# tick-shield-mk-1_2.net
KiCad netlist of a schematic drawn in EAGLE
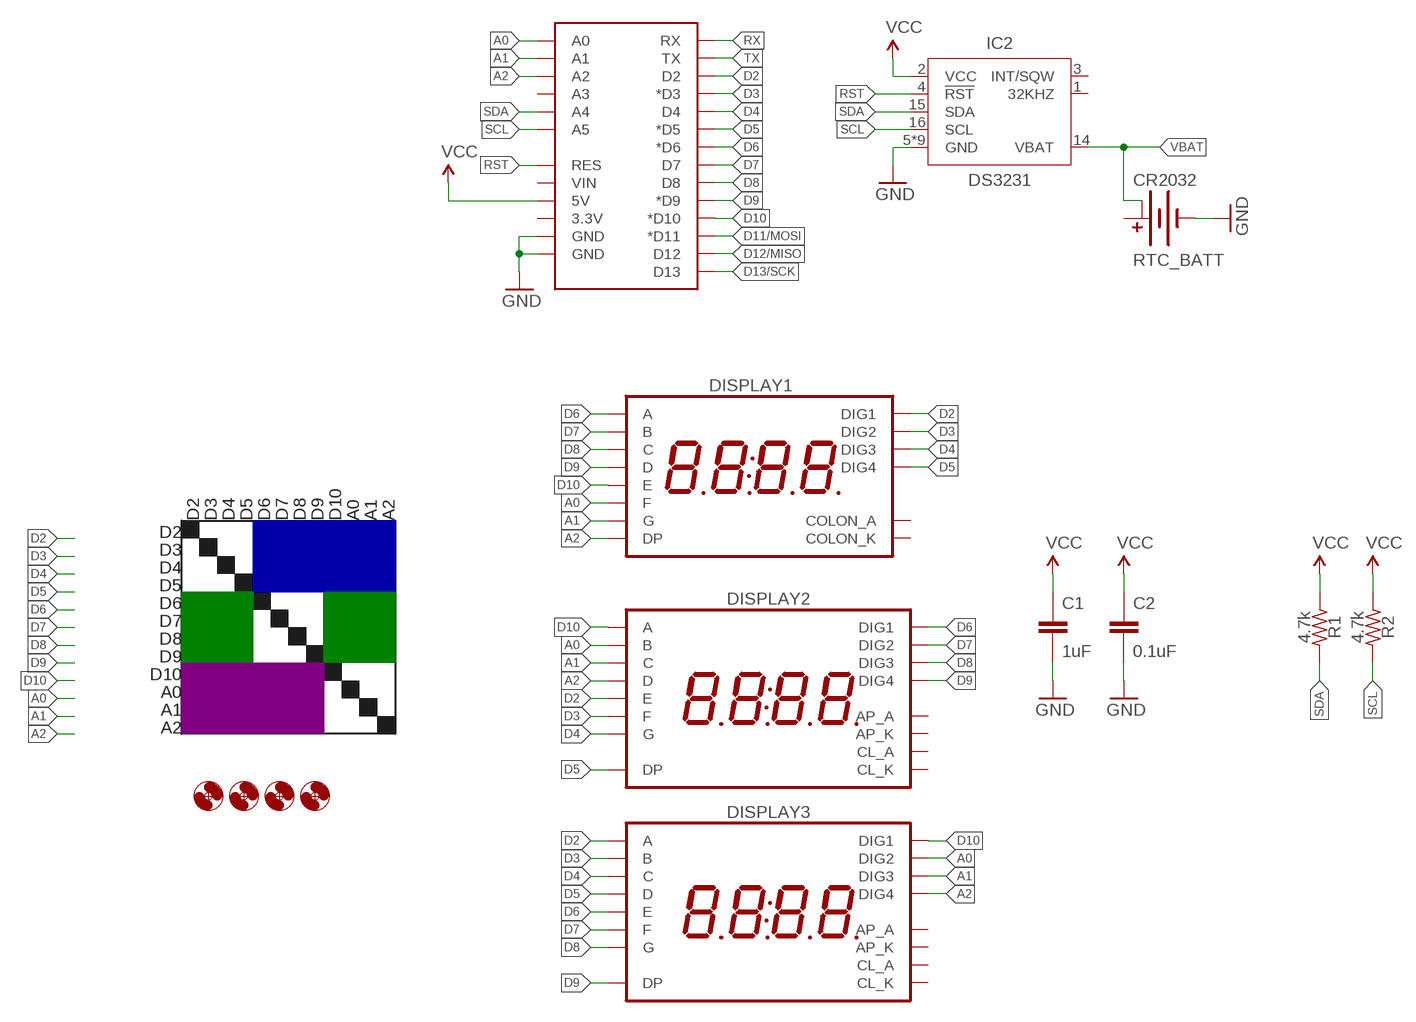
[diagram p0: schematic, sheet 1]

(export (version "E")
  (design (tool "Eeschema 10.0.6"))
  (components
    (comp (ref "C1")
      (value "1uF")
      (footprint "eagle-import:C025-024X044")
      (libsource (lib "eagle-import") (part "CAPACITOR-CERAMIC025-024X044"))
    )
    (comp (ref "C2")
      (value "0.1uF")
      (footprint "eagle-import:C0805")
      (libsource (lib "eagle-import") (part "CAPACITOR-CERAMICC0805"))
    )
    (comp (ref "DISPLAY1")
      (value "7SEG_4DIGIT_COLON14.2MM-CC-NS")
      (footprint "eagle-import:7SEG_4DIG_NS")
      (libsource (lib "eagle-import") (part "7SEG_4DIGIT_COLON14.2MM-CC-NS"))
    )
    (comp (ref "DISPLAY2")
      (value "7SEG_4DIGIT_COLON_APOS")
      (footprint "eagle-import:7SEG_4DIG_10MM")
      (libsource (lib "eagle-import") (part "7SEG_4DIGIT_COLON_APOS"))
    )
    (comp (ref "DISPLAY3")
      (value "7SEG_4DIGIT_COLON_APOS")
      (footprint "eagle-import:7SEG_4DIG_10MM")
      (libsource (lib "eagle-import") (part "7SEG_4DIGIT_COLON_APOS"))
    )
    (comp (ref "H1")
      (value "HOLE#2")
      (footprint "eagle-import:HOLE-#2")
      (libsource (lib "eagle-import") (part "HOLE#2"))
    )
    (comp (ref "H2")
      (value "HOLE#2")
      (footprint "eagle-import:HOLE-#2")
      (libsource (lib "eagle-import") (part "HOLE#2"))
    )
    (comp (ref "H3")
      (value "HOLE#2")
      (footprint "eagle-import:HOLE-#2")
      (libsource (lib "eagle-import") (part "HOLE#2"))
    )
    (comp (ref "H4")
      (value "HOLE#2")
      (footprint "eagle-import:HOLE-#2")
      (libsource (lib "eagle-import") (part "HOLE#2"))
    )
    (comp (ref "IC2")
      (value "DS3231")
      (footprint "eagle-import:SO16W")
      (libsource (lib "eagle-import") (part "DS3231"))
    )
    (comp (ref "R1")
      (value "4.7k")
      (footprint "eagle-import:RESISTOR-AXIAL-PTH-6.35MM")
      (libsource (lib "eagle-import") (part "RESISTORPTH-AXIAL-6.35MM"))
    )
    (comp (ref "R2")
      (value "4.7k")
      (footprint "eagle-import:RESISTOR-AXIAL-PTH-6.35MM")
      (libsource (lib "eagle-import") (part "RESISTORPTH-AXIAL-6.35MM"))
    )
    (comp (ref "RTC_BATT")
      (value "CR2032")
      (footprint "eagle-import:BATTCON_20MM_MINE")
      (libsource (lib "eagle-import") (part "BATTERY-COINCR2032_SMD"))
    )
    (comp (ref "U$1")
      (value "ARDUINO_SHIELD_SMALLER")
      (footprint "eagle-import:ARDUINO_SHIELD_NOOUTLINE_INSIDE_SMALLER")
      (libsource (lib "eagle-import") (part "ARDUINO_SHIELD_SMALLER"))
    )
  )
  (nets
    (net (code "1") (name "A0") (class "Default")
      (node (ref "DISPLAY1") (pin "P$12") (pinfunction "F_P$12") (pintype "passive"))
      (node (ref "DISPLAY2") (pin "16") (pinfunction "B_16") (pintype "passive"))
      (node (ref "DISPLAY3") (pin "2") (pinfunction "DIG2_2") (pintype "passive"))
      (node (ref "U$1") (pin "A0") (pinfunction "A0_A0") (pintype "bidirectional"))
    )
    (net (code "2") (name "A1") (class "Default")
      (node (ref "DISPLAY1") (pin "P$5") (pinfunction "G_P$5") (pintype "passive"))
      (node (ref "DISPLAY2") (pin "13") (pinfunction "C_13") (pintype "passive"))
      (node (ref "DISPLAY3") (pin "6") (pinfunction "DIG3_6") (pintype "passive"))
      (node (ref "U$1") (pin "A1") (pinfunction "A1_A1") (pintype "bidirectional"))
    )
    (net (code "3") (name "A2") (class "Default")
      (node (ref "DISPLAY1") (pin "P$3") (pinfunction "DP_P$3") (pintype "passive"))
      (node (ref "DISPLAY2") (pin "3") (pinfunction "D_3") (pintype "passive"))
      (node (ref "DISPLAY3") (pin "8") (pinfunction "DIG4_8") (pintype "passive"))
      (node (ref "U$1") (pin "A2") (pinfunction "A2_A2") (pintype "bidirectional"))
    )
    (net (code "4") (name "D2") (class "Default")
      (node (ref "DISPLAY1") (pin "P$14") (pinfunction "DIG1_P$14") (pintype "passive"))
      (node (ref "DISPLAY2") (pin "5") (pinfunction "E_5") (pintype "passive"))
      (node (ref "DISPLAY3") (pin "14") (pinfunction "A_14") (pintype "passive"))
      (node (ref "U$1") (pin "D2") (pinfunction "D2_D2") (pintype "bidirectional"))
    )
    (net (code "5") (name "D3") (class "Default")
      (node (ref "DISPLAY1") (pin "P$11") (pinfunction "DIG2_P$11") (pintype "passive"))
      (node (ref "DISPLAY2") (pin "11") (pinfunction "F_11") (pintype "passive"))
      (node (ref "DISPLAY3") (pin "16") (pinfunction "B_16") (pintype "passive"))
      (node (ref "U$1") (pin "D3") (pinfunction "*D3_D3") (pintype "bidirectional"))
    )
    (net (code "6") (name "D4") (class "Default")
      (node (ref "DISPLAY1") (pin "P$10") (pinfunction "DIG3_P$10") (pintype "passive"))
      (node (ref "DISPLAY2") (pin "15") (pinfunction "G_15") (pintype "passive"))
      (node (ref "DISPLAY3") (pin "13") (pinfunction "C_13") (pintype "passive"))
      (node (ref "U$1") (pin "D4") (pinfunction "D4_D4") (pintype "bidirectional"))
    )
    (net (code "7") (name "D5") (class "Default")
      (node (ref "DISPLAY1") (pin "P$6") (pinfunction "DIG4_P$6") (pintype "passive"))
      (node (ref "DISPLAY2") (pin "7") (pinfunction "DP_7") (pintype "passive"))
      (node (ref "DISPLAY3") (pin "3") (pinfunction "D_3") (pintype "passive"))
      (node (ref "U$1") (pin "D5") (pinfunction "*D5_D5") (pintype "bidirectional"))
    )
    (net (code "8") (name "D6") (class "Default")
      (node (ref "DISPLAY1") (pin "P$13") (pinfunction "A_P$13") (pintype "passive"))
      (node (ref "DISPLAY2") (pin "1") (pinfunction "DIG1_1") (pintype "passive"))
      (node (ref "DISPLAY3") (pin "5") (pinfunction "E_5") (pintype "passive"))
      (node (ref "U$1") (pin "D6") (pinfunction "*D6_D6") (pintype "bidirectional"))
    )
    (net (code "9") (name "D7") (class "Default")
      (node (ref "DISPLAY1") (pin "P$9") (pinfunction "B_P$9") (pintype "passive"))
      (node (ref "DISPLAY2") (pin "2") (pinfunction "DIG2_2") (pintype "passive"))
      (node (ref "DISPLAY3") (pin "11") (pinfunction "F_11") (pintype "passive"))
      (node (ref "U$1") (pin "D7") (pinfunction "D7_D7") (pintype "bidirectional"))
    )
    (net (code "10") (name "D8") (class "Default")
      (node (ref "DISPLAY1") (pin "P$4") (pinfunction "C_P$4") (pintype "passive"))
      (node (ref "DISPLAY2") (pin "6") (pinfunction "DIG3_6") (pintype "passive"))
      (node (ref "DISPLAY3") (pin "15") (pinfunction "G_15") (pintype "passive"))
      (node (ref "U$1") (pin "D8") (pinfunction "D8_D8") (pintype "bidirectional"))
    )
    (net (code "11") (name "D9") (class "Default")
      (node (ref "DISPLAY1") (pin "P$2") (pinfunction "D_P$2") (pintype "passive"))
      (node (ref "DISPLAY2") (pin "8") (pinfunction "DIG4_8") (pintype "passive"))
      (node (ref "DISPLAY3") (pin "7") (pinfunction "DP_7") (pintype "passive"))
      (node (ref "U$1") (pin "D9") (pinfunction "*D9_D9") (pintype "bidirectional"))
    )
    (net (code "12") (name "D10") (class "Default")
      (node (ref "DISPLAY1") (pin "P$1") (pinfunction "E_P$1") (pintype "passive"))
      (node (ref "DISPLAY2") (pin "14") (pinfunction "A_14") (pintype "passive"))
      (node (ref "DISPLAY3") (pin "1") (pinfunction "DIG1_1") (pintype "passive"))
      (node (ref "U$1") (pin "D10") (pinfunction "*D10_D10") (pintype "bidirectional"))
    )
    (net (code "13") (name "D11{slash}MOSI") (class "Default")
      (node (ref "U$1") (pin "D11") (pinfunction "*D11_D11") (pintype "bidirectional"))
    )
    (net (code "14") (name "D12{slash}MISO") (class "Default")
      (node (ref "U$1") (pin "D12") (pinfunction "D12_D12") (pintype "bidirectional"))
    )
    (net (code "15") (name "D13{slash}SCK") (class "Default")
      (node (ref "U$1") (pin "D13") (pinfunction "D13_D13") (pintype "bidirectional"))
    )
    (net (code "16") (name "GND") (class "Default")
      (node (ref "C1") (pin "2") (pinfunction "2_2") (pintype "passive"))
      (node (ref "C2") (pin "2") (pinfunction "2_2") (pintype "passive"))
      (node (ref "IC2") (pin "10") (pinfunction "GND_10") (pintype "bidirectional"))
      (node (ref "IC2") (pin "11") (pinfunction "GND_11") (pintype "bidirectional"))
      (node (ref "IC2") (pin "12") (pinfunction "GND_12") (pintype "bidirectional"))
      (node (ref "IC2") (pin "13") (pinfunction "GND_13") (pintype "bidirectional"))
      (node (ref "IC2") (pin "5") (pinfunction "GND_5") (pintype "bidirectional"))
      (node (ref "IC2") (pin "6") (pinfunction "GND_6") (pintype "bidirectional"))
      (node (ref "IC2") (pin "7") (pinfunction "GND_7") (pintype "bidirectional"))
      (node (ref "IC2") (pin "8") (pinfunction "GND_8") (pintype "bidirectional"))
      (node (ref "IC2") (pin "9") (pinfunction "GND_9") (pintype "bidirectional"))
      (node (ref "RTC_BATT") (pin "BOTTOM") (pinfunction "-_BOTTOM") (pintype "bidirectional"))
      (node (ref "U$1") (pin "GND@0") (pinfunction "GND_GND@0") (pintype "bidirectional"))
      (node (ref "U$1") (pin "GND@1") (pinfunction "GND_GND@1") (pintype "bidirectional"))
    )
    (net (code "17") (name "RST") (class "Default")
      (node (ref "IC2") (pin "4") (pinfunction "~{RST}_4") (pintype "bidirectional"))
      (node (ref "U$1") (pin "RES") (pinfunction "RES_RES") (pintype "bidirectional"))
    )
    (net (code "18") (name "RX") (class "Default")
      (node (ref "U$1") (pin "RX") (pinfunction "RX_RX") (pintype "bidirectional"))
    )
    (net (code "19") (name "SCL") (class "Default")
      (node (ref "IC2") (pin "16") (pinfunction "SCL_16") (pintype "bidirectional"))
      (node (ref "R2") (pin "P$2") (pinfunction "2_P$2") (pintype "passive"))
      (node (ref "U$1") (pin "A5") (pinfunction "A5_A5") (pintype "bidirectional"))
    )
    (net (code "20") (name "SDA") (class "Default")
      (node (ref "IC2") (pin "15") (pinfunction "SDA_15") (pintype "bidirectional"))
      (node (ref "R1") (pin "P$2") (pinfunction "2_P$2") (pintype "passive"))
      (node (ref "U$1") (pin "A4") (pinfunction "A4_A4") (pintype "bidirectional"))
    )
    (net (code "21") (name "TX") (class "Default")
      (node (ref "U$1") (pin "TX") (pinfunction "TX_TX") (pintype "bidirectional"))
    )
    (net (code "22") (name "VBAT") (class "Default")
      (node (ref "IC2") (pin "14") (pinfunction "VBAT_14") (pintype "bidirectional"))
      (node (ref "RTC_BATT") (pin "TOP@2") (pinfunction "+1_TOP@2") (pintype "bidirectional"))
    )
    (net (code "23") (name "VCC") (class "Default")
      (node (ref "C1") (pin "1") (pinfunction "1_1") (pintype "passive"))
      (node (ref "C2") (pin "1") (pinfunction "1_1") (pintype "passive"))
      (node (ref "IC2") (pin "2") (pinfunction "VCC_2") (pintype "bidirectional"))
      (node (ref "R1") (pin "P$1") (pinfunction "1_P$1") (pintype "passive"))
      (node (ref "R2") (pin "P$1") (pinfunction "1_P$1") (pintype "passive"))
      (node (ref "U$1") (pin "5V") (pinfunction "5V_5V") (pintype "bidirectional"))
    )
    (net (code "24") (name "unconnected-(DISPLAY1-COLON_A-PadP$8)") (class "Default")
      (node (ref "DISPLAY1") (pin "P$8") (pinfunction "COLON_A_P$8") (pintype "passive"))
    )
    (net (code "25") (name "unconnected-(DISPLAY1-COLON_K-PadP$7)") (class "Default")
      (node (ref "DISPLAY1") (pin "P$7") (pinfunction "COLON_K_P$7") (pintype "passive"))
    )
    (net (code "26") (name "unconnected-(DISPLAY2-AP_A-Pad10)") (class "Default")
      (node (ref "DISPLAY2") (pin "10") (pinfunction "AP_A_10") (pintype "bidirectional"))
    )
    (net (code "27") (name "unconnected-(DISPLAY2-AP_K-Pad9)") (class "Default")
      (node (ref "DISPLAY2") (pin "9") (pinfunction "AP_K_9") (pintype "bidirectional"))
    )
    (net (code "28") (name "unconnected-(DISPLAY2-CL_A-Pad4)") (class "Default")
      (node (ref "DISPLAY2") (pin "4") (pinfunction "CL_A_4") (pintype "passive"))
    )
    (net (code "29") (name "unconnected-(DISPLAY2-CL_K-Pad12)") (class "Default")
      (node (ref "DISPLAY2") (pin "12") (pinfunction "CL_K_12") (pintype "passive"))
    )
    (net (code "30") (name "unconnected-(DISPLAY3-AP_A-Pad10)") (class "Default")
      (node (ref "DISPLAY3") (pin "10") (pinfunction "AP_A_10") (pintype "bidirectional"))
    )
    (net (code "31") (name "unconnected-(DISPLAY3-AP_K-Pad9)") (class "Default")
      (node (ref "DISPLAY3") (pin "9") (pinfunction "AP_K_9") (pintype "bidirectional"))
    )
    (net (code "32") (name "unconnected-(DISPLAY3-CL_A-Pad4)") (class "Default")
      (node (ref "DISPLAY3") (pin "4") (pinfunction "CL_A_4") (pintype "passive"))
    )
    (net (code "33") (name "unconnected-(DISPLAY3-CL_K-Pad12)") (class "Default")
      (node (ref "DISPLAY3") (pin "12") (pinfunction "CL_K_12") (pintype "passive"))
    )
    (net (code "34") (name "unconnected-(IC2-32KHZ-Pad1)") (class "Default")
      (node (ref "IC2") (pin "1") (pinfunction "32KHZ_1") (pintype "bidirectional"))
    )
    (net (code "35") (name "unconnected-(IC2-INT{slash}SQW-Pad3)") (class "Default")
      (node (ref "IC2") (pin "3") (pinfunction "INT/SQW_3") (pintype "bidirectional"))
    )
    (net (code "36") (name "unconnected-(RTC_BATT-+-PadTOP@1)") (class "Default")
      (node (ref "RTC_BATT") (pin "TOP@1") (pinfunction "+_TOP@1") (pintype "bidirectional"))
    )
    (net (code "37") (name "unconnected-(U$1-Pad3.3V)") (class "Default")
      (node (ref "U$1") (pin "3.3V") (pinfunction "3.3V_3.3V") (pintype "bidirectional"))
    )
    (net (code "38") (name "unconnected-(U$1-PadA3)") (class "Default")
      (node (ref "U$1") (pin "A3") (pinfunction "A3_A3") (pintype "bidirectional"))
    )
    (net (code "39") (name "unconnected-(U$1-PadVIN)") (class "Default")
      (node (ref "U$1") (pin "VIN") (pinfunction "VIN_VIN") (pintype "bidirectional"))
    )
  )
)
